# murdock_conn_v1.net
KiCad netlist of a schematic drawn in EAGLE
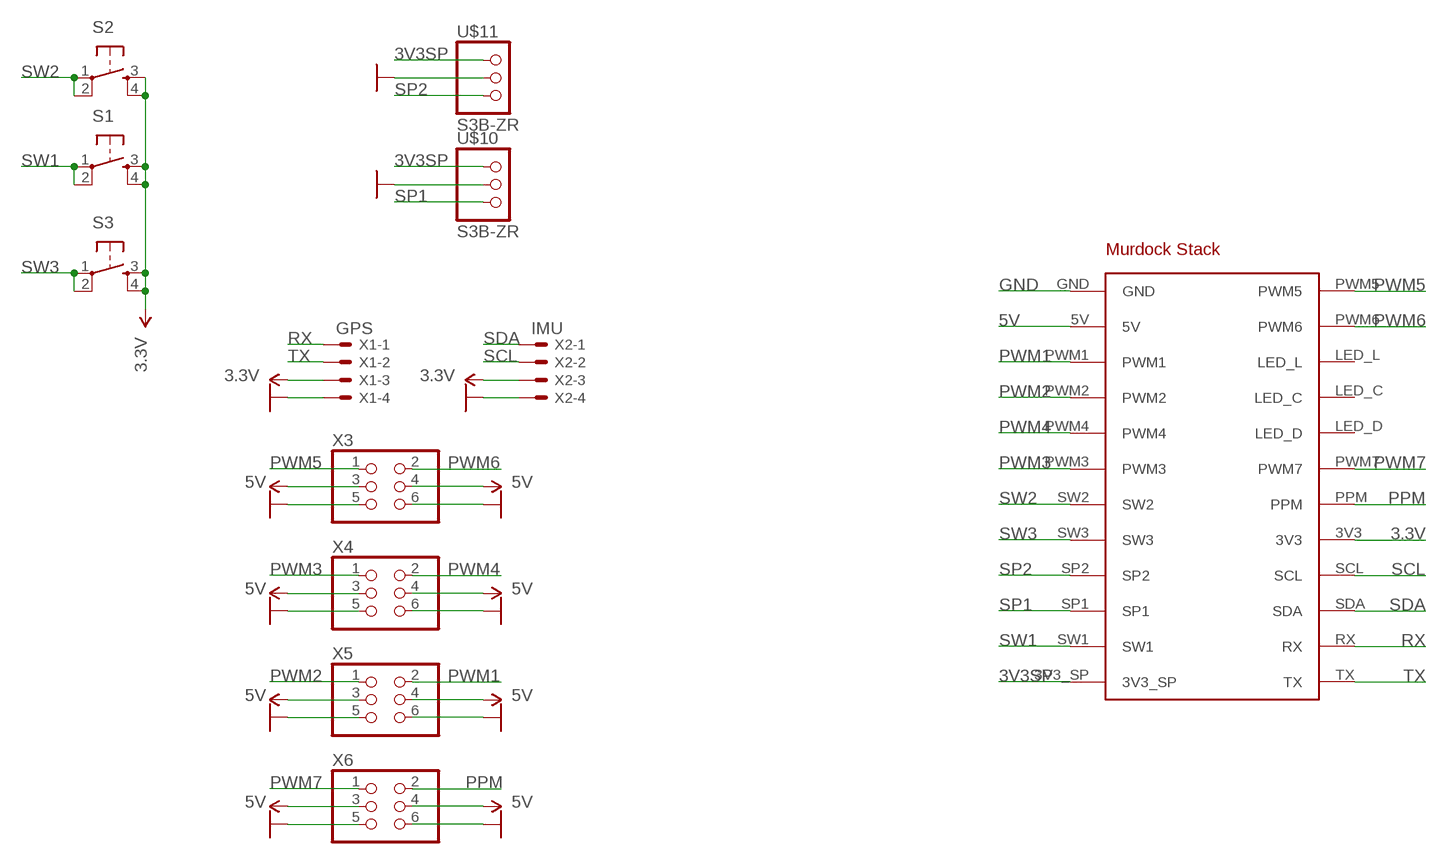
[diagram p0: schematic, sheet 1]

(export (version "E")
  (design (tool "Eeschema 10.0.6"))
  (components
    (comp (ref "S1")
      (value "LSH")
      (footprint "eagle-import:LSH")
      (libsource (lib "eagle-import") (part "LSH"))
    )
    (comp (ref "S2")
      (value "LSH")
      (footprint "eagle-import:LSH")
      (libsource (lib "eagle-import") (part "LSH"))
    )
    (comp (ref "S3")
      (value "LSH")
      (footprint "eagle-import:LSH")
      (libsource (lib "eagle-import") (part "LSH"))
    )
    (comp (ref "U$10")
      (value "S3B-ZR")
      (footprint "eagle-import:S3B-ZR")
      (libsource (lib "eagle-import") (part "S3B-ZR"))
    )
    (comp (ref "U$11")
      (value "S3B-ZR")
      (footprint "eagle-import:S3B-ZR")
      (libsource (lib "eagle-import") (part "S3B-ZR"))
    )
    (comp (ref "X1")
      (value "GPS")
      (footprint "eagle-import:70553-04")
      (libsource (lib "eagle-import") (part "C-GRID-04-70553"))
    )
    (comp (ref "X2")
      (value "IMU")
      (footprint "eagle-import:70553-04")
      (libsource (lib "eagle-import") (part "C-GRID-04-70553"))
    )
    (comp (ref "X3")
      (value "PINHD-2X3/90")
      (footprint "eagle-import:2X03_90")
      (libsource (lib "eagle-import") (part "PINHD-2X3/90"))
    )
    (comp (ref "X4")
      (value "PINHD-2X3/90")
      (footprint "eagle-import:2X03_90")
      (libsource (lib "eagle-import") (part "PINHD-2X3/90"))
    )
    (comp (ref "X5")
      (value "PINHD-2X3/90")
      (footprint "eagle-import:2X03_90")
      (libsource (lib "eagle-import") (part "PINHD-2X3/90"))
    )
    (comp (ref "X6")
      (value "PINHD-2X3/90")
      (footprint "eagle-import:2X03_90")
      (libsource (lib "eagle-import") (part "PINHD-2X3/90"))
    )
    (comp (ref "X7")
      (value "MURDOCK_STACK")
      (footprint "eagle-import:MURDOCK_STACK")
      (libsource (lib "eagle-import") (part "MURDOCK_STACK"))
    )
  )
  (nets
    (net (code "1") (name "/3V3SP") (class "Default")
      (node (ref "U$10") (pin "1") (pinfunction "1_1") (pintype "bidirectional"))
      (node (ref "U$11") (pin "1") (pinfunction "1_1") (pintype "bidirectional"))
      (node (ref "X7") (pin "3V3_SP") (pinfunction "3V3_SP_3V3_SP") (pintype "bidirectional"))
    )
    (net (code "2") (name "/PPM") (class "Default")
      (node (ref "X6") (pin "2") (pinfunction "2_2") (pintype "passive"))
      (node (ref "X7") (pin "PPM") (pinfunction "PPM_PPM") (pintype "bidirectional"))
    )
    (net (code "3") (name "/PWM1") (class "Default")
      (node (ref "X5") (pin "2") (pinfunction "2_2") (pintype "passive"))
      (node (ref "X7") (pin "PWM1") (pinfunction "PWM1_PWM1") (pintype "bidirectional"))
    )
    (net (code "4") (name "/PWM2") (class "Default")
      (node (ref "X5") (pin "1") (pinfunction "1_1") (pintype "passive"))
      (node (ref "X7") (pin "PWM2") (pinfunction "PWM2_PWM2") (pintype "bidirectional"))
    )
    (net (code "5") (name "/PWM3") (class "Default")
      (node (ref "X4") (pin "1") (pinfunction "1_1") (pintype "passive"))
      (node (ref "X7") (pin "PWM3") (pinfunction "PWM3_PWM3") (pintype "bidirectional"))
    )
    (net (code "6") (name "/PWM4") (class "Default")
      (node (ref "X4") (pin "2") (pinfunction "2_2") (pintype "passive"))
      (node (ref "X7") (pin "PWM4") (pinfunction "PWM4_PWM4") (pintype "bidirectional"))
    )
    (net (code "7") (name "/PWM5") (class "Default")
      (node (ref "X3") (pin "1") (pinfunction "1_1") (pintype "passive"))
      (node (ref "X7") (pin "PWM5") (pinfunction "PWM5_PWM5") (pintype "bidirectional"))
    )
    (net (code "8") (name "/PWM6") (class "Default")
      (node (ref "X3") (pin "2") (pinfunction "2_2") (pintype "passive"))
      (node (ref "X7") (pin "PWM6") (pinfunction "PWM6_PWM6") (pintype "bidirectional"))
    )
    (net (code "9") (name "/PWM7") (class "Default")
      (node (ref "X6") (pin "1") (pinfunction "1_1") (pintype "passive"))
      (node (ref "X7") (pin "PWM7") (pinfunction "PWM7_PWM7") (pintype "bidirectional"))
    )
    (net (code "10") (name "/RX") (class "Default")
      (node (ref "X1") (pin "1") (pinfunction "S_1") (pintype "passive"))
      (node (ref "X7") (pin "RX") (pinfunction "RX_RX") (pintype "bidirectional"))
    )
    (net (code "11") (name "/SCL") (class "Default")
      (node (ref "X2") (pin "2") (pinfunction "S_2") (pintype "passive"))
      (node (ref "X7") (pin "SCL") (pinfunction "SCL_SCL") (pintype "bidirectional"))
    )
    (net (code "12") (name "/SDA") (class "Default")
      (node (ref "X2") (pin "1") (pinfunction "S_1") (pintype "passive"))
      (node (ref "X7") (pin "SDA") (pinfunction "SDA_SDA") (pintype "bidirectional"))
    )
    (net (code "13") (name "/SP1") (class "Default")
      (node (ref "U$10") (pin "3") (pinfunction "3_3") (pintype "bidirectional"))
      (node (ref "X7") (pin "SP1") (pinfunction "SP1_SP1") (pintype "bidirectional"))
    )
    (net (code "14") (name "/SP2") (class "Default")
      (node (ref "U$11") (pin "3") (pinfunction "3_3") (pintype "bidirectional"))
      (node (ref "X7") (pin "SP2") (pinfunction "SP2_SP2") (pintype "bidirectional"))
    )
    (net (code "15") (name "/SW1") (class "Default")
      (node (ref "S1") (pin "1") (pinfunction "1_1") (pintype "passive"))
      (node (ref "S1") (pin "2") (pinfunction "2_2") (pintype "passive"))
      (node (ref "X7") (pin "SW1") (pinfunction "SW1_SW1") (pintype "bidirectional"))
    )
    (net (code "16") (name "/SW2") (class "Default")
      (node (ref "S2") (pin "1") (pinfunction "1_1") (pintype "passive"))
      (node (ref "S2") (pin "2") (pinfunction "2_2") (pintype "passive"))
      (node (ref "X7") (pin "SW2") (pinfunction "SW2_SW2") (pintype "bidirectional"))
    )
    (net (code "17") (name "/SW3") (class "Default")
      (node (ref "S3") (pin "1") (pinfunction "1_1") (pintype "passive"))
      (node (ref "S3") (pin "2") (pinfunction "2_2") (pintype "passive"))
      (node (ref "X7") (pin "SW3") (pinfunction "SW3_SW3") (pintype "bidirectional"))
    )
    (net (code "18") (name "/TX") (class "Default")
      (node (ref "X1") (pin "2") (pinfunction "S_2") (pintype "passive"))
      (node (ref "X7") (pin "TX") (pinfunction "TX_TX") (pintype "bidirectional"))
    )
    (net (code "19") (name "3.3V") (class "Default")
      (node (ref "S1") (pin "3") (pinfunction "3_3") (pintype "passive"))
      (node (ref "S1") (pin "4") (pinfunction "4_4") (pintype "passive"))
      (node (ref "S2") (pin "3") (pinfunction "3_3") (pintype "passive"))
      (node (ref "S2") (pin "4") (pinfunction "4_4") (pintype "passive"))
      (node (ref "S3") (pin "3") (pinfunction "3_3") (pintype "passive"))
      (node (ref "S3") (pin "4") (pinfunction "4_4") (pintype "passive"))
      (node (ref "X1") (pin "3") (pinfunction "S_3") (pintype "passive"))
      (node (ref "X2") (pin "3") (pinfunction "S_3") (pintype "passive"))
      (node (ref "X7") (pin "3V3") (pinfunction "3V3_3V3") (pintype "bidirectional"))
    )
    (net (code "20") (name "5V") (class "Default")
      (node (ref "X3") (pin "3") (pinfunction "3_3") (pintype "passive"))
      (node (ref "X3") (pin "4") (pinfunction "4_4") (pintype "passive"))
      (node (ref "X4") (pin "3") (pinfunction "3_3") (pintype "passive"))
      (node (ref "X4") (pin "4") (pinfunction "4_4") (pintype "passive"))
      (node (ref "X5") (pin "3") (pinfunction "3_3") (pintype "passive"))
      (node (ref "X5") (pin "4") (pinfunction "4_4") (pintype "passive"))
      (node (ref "X6") (pin "3") (pinfunction "3_3") (pintype "passive"))
      (node (ref "X6") (pin "4") (pinfunction "4_4") (pintype "passive"))
      (node (ref "X7") (pin "5V") (pinfunction "5V_5V") (pintype "bidirectional"))
    )
    (net (code "21") (name "GND") (class "Default")
      (node (ref "U$10") (pin "2") (pinfunction "2_2") (pintype "bidirectional"))
      (node (ref "U$11") (pin "2") (pinfunction "2_2") (pintype "bidirectional"))
      (node (ref "X1") (pin "4") (pinfunction "S_4") (pintype "passive"))
      (node (ref "X2") (pin "4") (pinfunction "S_4") (pintype "passive"))
      (node (ref "X3") (pin "5") (pinfunction "5_5") (pintype "passive"))
      (node (ref "X3") (pin "6") (pinfunction "6_6") (pintype "passive"))
      (node (ref "X4") (pin "5") (pinfunction "5_5") (pintype "passive"))
      (node (ref "X4") (pin "6") (pinfunction "6_6") (pintype "passive"))
      (node (ref "X5") (pin "5") (pinfunction "5_5") (pintype "passive"))
      (node (ref "X5") (pin "6") (pinfunction "6_6") (pintype "passive"))
      (node (ref "X6") (pin "5") (pinfunction "5_5") (pintype "passive"))
      (node (ref "X6") (pin "6") (pinfunction "6_6") (pintype "passive"))
      (node (ref "X7") (pin "GND") (pinfunction "GND_GND") (pintype "bidirectional"))
    )
    (net (code "22") (name "unconnected-(X7-PadLED_C)") (class "Default")
      (node (ref "X7") (pin "LED_C") (pinfunction "LED_C_LED_C") (pintype "bidirectional"))
    )
    (net (code "23") (name "unconnected-(X7-PadLED_D)") (class "Default")
      (node (ref "X7") (pin "LED_D") (pinfunction "LED_D_LED_D") (pintype "bidirectional"))
    )
    (net (code "24") (name "unconnected-(X7-PadLED_L)") (class "Default")
      (node (ref "X7") (pin "LED_L") (pinfunction "LED_L_LED_L") (pintype "bidirectional"))
    )
  )
)
